# ATMEGA328P.net
KiCad netlist of a schematic drawn in Altium Designer
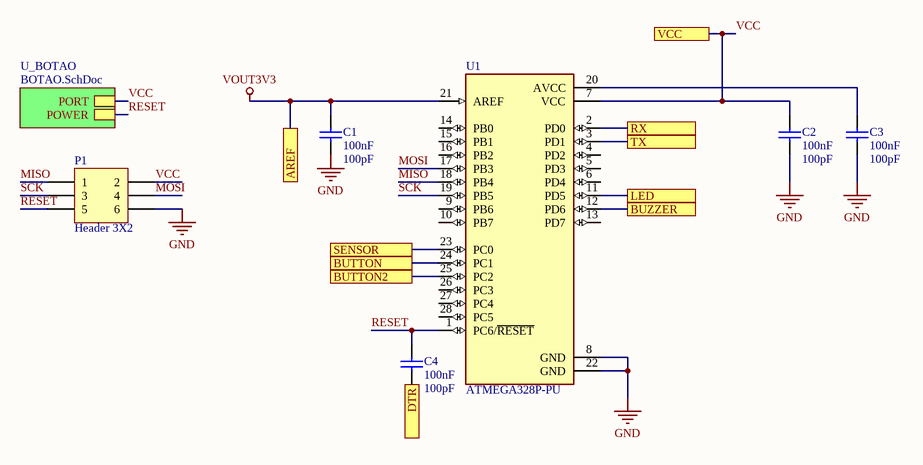
[diagram p0: ATMEGA328P.SchDoc]

(export (version "E")
  (design (tool "Eeschema 10.0.6"))
  (components
    (comp (ref "C1")
      (value "100nF")
      (footprint "RAD-0.3")
      (description "Capacitor")
      (fields (field (name "ALTIUM_VALUE") "100pF") (field (name "PUBLISHER") "Altium Limited"))
      (libsource (lib "Miscellaneous Devices") (part "Cap"))
    )
    (comp (ref "C2")
      (value "100nF")
      (footprint "RAD-0.3")
      (description "Capacitor")
      (fields (field (name "ALTIUM_VALUE") "100pF") (field (name "PUBLISHER") "Altium Limited"))
      (libsource (lib "Miscellaneous Devices") (part "Cap"))
    )
    (comp (ref "C3")
      (value "100nF")
      (footprint "RAD-0.3")
      (description "Capacitor")
      (fields (field (name "ALTIUM_VALUE") "100pF") (field (name "PUBLISHER") "Altium Limited"))
      (libsource (lib "Miscellaneous Devices") (part "Cap"))
    )
    (comp (ref "C4")
      (value "100nF")
      (footprint "RAD-0.3")
      (description "Capacitor")
      (fields (field (name "ALTIUM_VALUE") "100pF") (field (name "PUBLISHER") "Altium Limited"))
      (libsource (lib "Miscellaneous Devices") (part "Cap"))
    )
    (comp (ref "P1")
      (value "Header 3X2")
      (footprint "HDR2X3")
      (description "Header, 3-Pin, Dual row")
      (fields (field (name "PUBLISHER") "Altium Limited"))
      (libsource (lib "Miscellaneous Connectors") (part "Header 3X2"))
    )
    (comp (ref "U1")
      (value "ATMEGA328P-PU")
      (footprint "ATMEGA328P-PU:DIP794W46P254L2967H457Q28B")
      (description "ATmega Series 20 MHz 32 KB Flash 2 KB SRAM 8-Bit Microcontroller - DIP-28")
      (libsource (lib "ATMEGA328P-PU") (part "ATMEGA328P-PU"))
    )
  )
  (nets
    (net (code "1") (name "/BUTTON") (class "Default")
      (node (ref "U1") (pin "24") (pinfunction "PC1_24") (pintype "bidirectional"))
    )
    (net (code "2") (name "/BUTTON2") (class "Default")
      (node (ref "U1") (pin "25") (pinfunction "PC2_25") (pintype "bidirectional"))
    )
    (net (code "3") (name "/BUZZER") (class "Default")
      (node (ref "U1") (pin "12") (pinfunction "PD6_12") (pintype "bidirectional"))
    )
    (net (code "4") (name "/DTR") (class "Default")
      (node (ref "C4") (pin "1") (pinfunction "1_1") (pintype "passive"))
    )
    (net (code "5") (name "/LED") (class "Default")
      (node (ref "U1") (pin "11") (pinfunction "PD5_11") (pintype "bidirectional"))
    )
    (net (code "6") (name "/MISO") (class "Default")
      (node (ref "P1") (pin "1") (pinfunction "1_1") (pintype "passive"))
      (node (ref "U1") (pin "18") (pinfunction "PB4_18") (pintype "bidirectional"))
    )
    (net (code "7") (name "/MOSI") (class "Default")
      (node (ref "P1") (pin "4") (pinfunction "4_4") (pintype "passive"))
      (node (ref "U1") (pin "17") (pinfunction "PB3_17") (pintype "bidirectional"))
    )
    (net (code "8") (name "/RESET") (class "Default")
      (node (ref "C4") (pin "2") (pinfunction "2_2") (pintype "passive"))
      (node (ref "P1") (pin "5") (pinfunction "5_5") (pintype "passive"))
      (node (ref "U1") (pin "1") (pinfunction "PC6/~{RESET}_1") (pintype "bidirectional"))
    )
    (net (code "9") (name "/RX") (class "Default")
      (node (ref "U1") (pin "2") (pinfunction "PD0_2") (pintype "bidirectional"))
    )
    (net (code "10") (name "/SCK") (class "Default")
      (node (ref "P1") (pin "3") (pinfunction "3_3") (pintype "passive"))
      (node (ref "U1") (pin "19") (pinfunction "PB5_19") (pintype "bidirectional"))
    )
    (net (code "11") (name "/SENSOR") (class "Default")
      (node (ref "U1") (pin "23") (pinfunction "PC0_23") (pintype "bidirectional"))
    )
    (net (code "12") (name "/TX") (class "Default")
      (node (ref "U1") (pin "3") (pinfunction "PD1_3") (pintype "bidirectional"))
    )
    (net (code "13") (name "/VCC") (class "Default")
      (node (ref "C2") (pin "2") (pinfunction "2_2") (pintype "passive"))
      (node (ref "P1") (pin "2") (pinfunction "2_2") (pintype "passive"))
      (node (ref "U1") (pin "7") (pinfunction "VCC_7") (pintype "power_in"))
    )
    (net (code "14") (name "GND") (class "Default")
      (node (ref "C1") (pin "1") (pinfunction "1_1") (pintype "passive"))
      (node (ref "C2") (pin "1") (pinfunction "1_1") (pintype "passive"))
      (node (ref "C3") (pin "1") (pinfunction "1_1") (pintype "passive"))
      (node (ref "P1") (pin "6") (pinfunction "6_6") (pintype "passive"))
      (node (ref "U1") (pin "22") (pinfunction "GND_22") (pintype "power_in"))
      (node (ref "U1") (pin "8") (pinfunction "GND_8") (pintype "power_in"))
    )
    (net (code "15") (name "Net-(U1-AVCC)") (class "Default")
      (node (ref "C3") (pin "2") (pinfunction "2_2") (pintype "passive"))
      (node (ref "U1") (pin "20") (pinfunction "AVCC_20") (pintype "power_in"))
    )
    (net (code "16") (name "VOUT3V3") (class "Default")
      (node (ref "C1") (pin "2") (pinfunction "2_2") (pintype "passive"))
      (node (ref "U1") (pin "21") (pinfunction "AREF_21") (pintype "input"))
    )
    (net (code "17") (name "unconnected-(U1-PB0-Pad14)") (class "Default")
      (node (ref "U1") (pin "14") (pinfunction "PB0_14") (pintype "bidirectional"))
    )
    (net (code "18") (name "unconnected-(U1-PB1-Pad15)") (class "Default")
      (node (ref "U1") (pin "15") (pinfunction "PB1_15") (pintype "bidirectional"))
    )
    (net (code "19") (name "unconnected-(U1-PB2-Pad16)") (class "Default")
      (node (ref "U1") (pin "16") (pinfunction "PB2_16") (pintype "bidirectional"))
    )
    (net (code "20") (name "unconnected-(U1-PB6-Pad9)") (class "Default")
      (node (ref "U1") (pin "9") (pinfunction "PB6_9") (pintype "bidirectional"))
    )
    (net (code "21") (name "unconnected-(U1-PB7-Pad10)") (class "Default")
      (node (ref "U1") (pin "10") (pinfunction "PB7_10") (pintype "bidirectional"))
    )
    (net (code "22") (name "unconnected-(U1-PC3-Pad26)") (class "Default")
      (node (ref "U1") (pin "26") (pinfunction "PC3_26") (pintype "bidirectional"))
    )
    (net (code "23") (name "unconnected-(U1-PC4-Pad27)") (class "Default")
      (node (ref "U1") (pin "27") (pinfunction "PC4_27") (pintype "bidirectional"))
    )
    (net (code "24") (name "unconnected-(U1-PC5-Pad28)") (class "Default")
      (node (ref "U1") (pin "28") (pinfunction "PC5_28") (pintype "bidirectional"))
    )
    (net (code "25") (name "unconnected-(U1-PD2-Pad4)") (class "Default")
      (node (ref "U1") (pin "4") (pinfunction "PD2_4") (pintype "bidirectional"))
    )
    (net (code "26") (name "unconnected-(U1-PD3-Pad5)") (class "Default")
      (node (ref "U1") (pin "5") (pinfunction "PD3_5") (pintype "bidirectional"))
    )
    (net (code "27") (name "unconnected-(U1-PD4-Pad6)") (class "Default")
      (node (ref "U1") (pin "6") (pinfunction "PD4_6") (pintype "bidirectional"))
    )
    (net (code "28") (name "unconnected-(U1-PD7-Pad13)") (class "Default")
      (node (ref "U1") (pin "13") (pinfunction "PD7_13") (pintype "bidirectional"))
    )
  )
)
